# rfid-shield.net
KiCad netlist of a schematic drawn in EAGLE
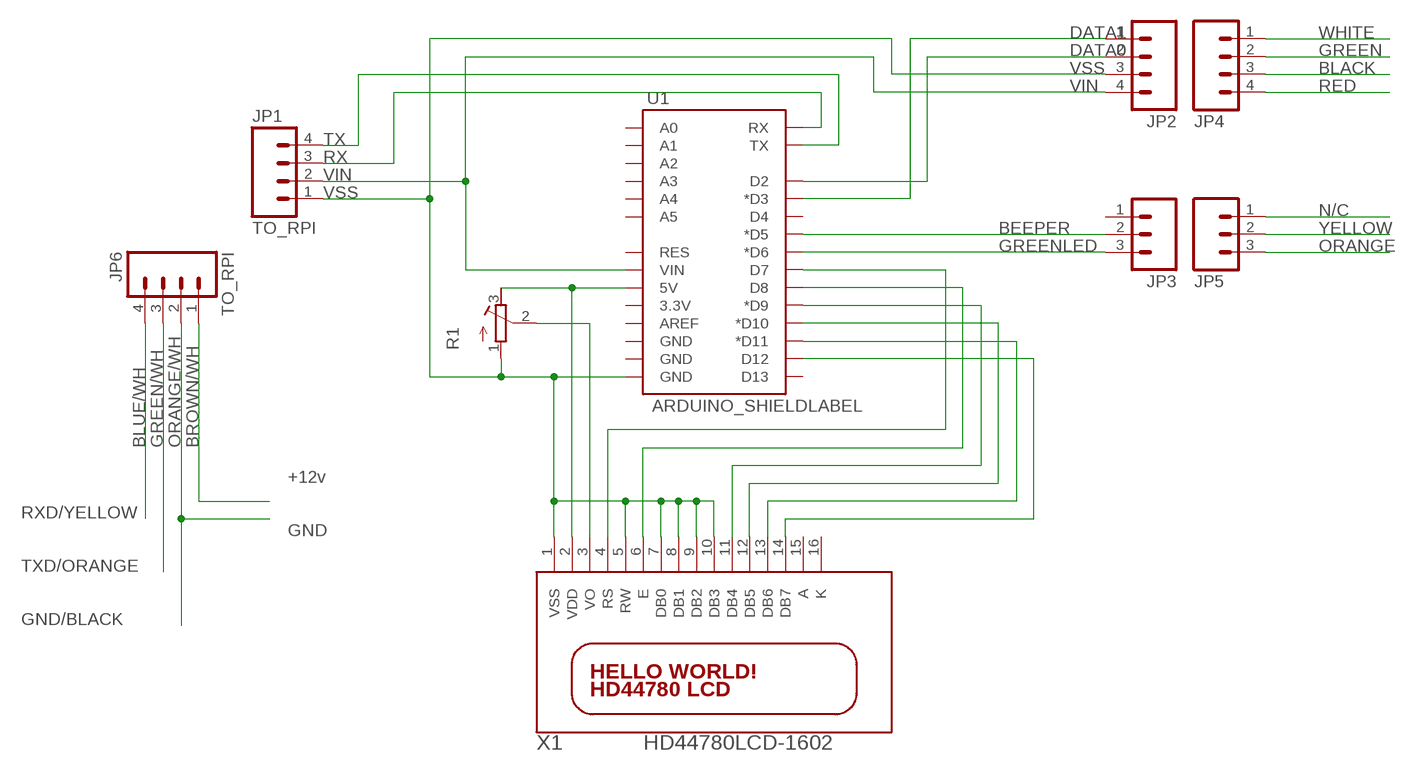
[diagram p0: schematic, sheet 1]

(export (version "E")
  (design (tool "Eeschema 10.0.6"))
  (components
    (comp (ref "JP1")
      (value "TO_RPI")
      (footprint "eagle-import:1X04_NO_SILK")
      (libsource (lib "eagle-import") (part "M041X04_NO_SILK"))
    )
    (comp (ref "JP2")
      (value "M041X04_NO_SILK")
      (footprint "eagle-import:1X04_NO_SILK")
      (libsource (lib "eagle-import") (part "M041X04_NO_SILK"))
    )
    (comp (ref "JP3")
      (value "M031X03_NO_SILK")
      (footprint "eagle-import:1X03_NO_SILK")
      (libsource (lib "eagle-import") (part "M031X03_NO_SILK"))
    )
    (comp (ref "JP4")
      (value "M041X04_NO_SILK")
      (footprint "eagle-import:1X04_NO_SILK")
      (libsource (lib "eagle-import") (part "M041X04_NO_SILK"))
    )
    (comp (ref "JP5")
      (value "M031X03_NO_SILK")
      (footprint "eagle-import:1X03_NO_SILK")
      (libsource (lib "eagle-import") (part "M031X03_NO_SILK"))
    )
    (comp (ref "JP6")
      (value "TO_RPI")
      (footprint "eagle-import:1X04_NO_SILK")
      (libsource (lib "eagle-import") (part "M041X04_NO_SILK"))
    )
    (comp (ref "R1")
      (value "R-TRIMMCVR42A")
      (footprint "eagle-import:RTRIMCVR42A")
      (libsource (lib "eagle-import") (part "R-TRIMMCVR42A"))
    )
    (comp (ref "U1")
      (value "ARDUINO_SHIELDLABEL")
      (footprint "eagle-import:DUEMILANOVE_SHIELD")
      (libsource (lib "eagle-import") (part "ARDUINO_SHIELDLABEL"))
    )
    (comp (ref "X1")
      (value "HD44780LCD-1602")
      (footprint "eagle-import:LCD1602")
      (libsource (lib "eagle-import") (part "HD44780LCD-1602"))
    )
  )
  (nets
    (net (code "1") (name "/BEEPER") (class "Default")
      (node (ref "JP3") (pin "2") (pinfunction "2_2") (pintype "passive"))
      (node (ref "U1") (pin "D5") (pinfunction "*D5_D5") (pintype "bidirectional"))
    )
    (net (code "2") (name "/BLACK") (class "Default")
      (node (ref "JP4") (pin "3") (pinfunction "3_3") (pintype "passive"))
    )
    (net (code "3") (name "/BLUE{slash}WH") (class "Default")
      (node (ref "JP6") (pin "4") (pinfunction "4_4") (pintype "passive"))
    )
    (net (code "4") (name "/BROWN{slash}WH") (class "Default")
      (node (ref "JP6") (pin "1") (pinfunction "1_1") (pintype "passive"))
    )
    (net (code "5") (name "/DATA0") (class "Default")
      (node (ref "JP2") (pin "2") (pinfunction "2_2") (pintype "passive"))
      (node (ref "U1") (pin "D2") (pinfunction "D2_D2") (pintype "bidirectional"))
    )
    (net (code "6") (name "/DATA1") (class "Default")
      (node (ref "JP2") (pin "1") (pinfunction "1_1") (pintype "passive"))
      (node (ref "U1") (pin "D3") (pinfunction "*D3_D3") (pintype "bidirectional"))
    )
    (net (code "7") (name "/GREEN") (class "Default")
      (node (ref "JP4") (pin "2") (pinfunction "2_2") (pintype "passive"))
    )
    (net (code "8") (name "/GREENLED") (class "Default")
      (node (ref "JP3") (pin "3") (pinfunction "3_3") (pintype "passive"))
      (node (ref "U1") (pin "D6") (pinfunction "*D6_D6") (pintype "bidirectional"))
    )
    (net (code "9") (name "/GREEN{slash}WH") (class "Default")
      (node (ref "JP6") (pin "3") (pinfunction "3_3") (pintype "passive"))
    )
    (net (code "10") (name "/N{slash}C") (class "Default")
      (node (ref "JP5") (pin "1") (pinfunction "1_1") (pintype "passive"))
    )
    (net (code "11") (name "/ORANGE") (class "Default")
      (node (ref "JP5") (pin "3") (pinfunction "3_3") (pintype "passive"))
    )
    (net (code "12") (name "/ORANGE{slash}WH") (class "Default")
      (node (ref "JP6") (pin "2") (pinfunction "2_2") (pintype "passive"))
    )
    (net (code "13") (name "/RED") (class "Default")
      (node (ref "JP4") (pin "4") (pinfunction "4_4") (pintype "passive"))
    )
    (net (code "14") (name "/RX") (class "Default")
      (node (ref "JP1") (pin "3") (pinfunction "3_3") (pintype "passive"))
      (node (ref "U1") (pin "RX") (pinfunction "RX_RX") (pintype "bidirectional"))
    )
    (net (code "15") (name "/TX") (class "Default")
      (node (ref "JP1") (pin "4") (pinfunction "4_4") (pintype "passive"))
      (node (ref "U1") (pin "TX") (pinfunction "TX_TX") (pintype "bidirectional"))
    )
    (net (code "16") (name "/VIN") (class "Default")
      (node (ref "JP1") (pin "2") (pinfunction "2_2") (pintype "passive"))
      (node (ref "JP2") (pin "4") (pinfunction "4_4") (pintype "passive"))
      (node (ref "U1") (pin "VIN") (pinfunction "VIN_VIN") (pintype "bidirectional"))
    )
    (net (code "17") (name "/VSS") (class "Default")
      (node (ref "JP1") (pin "1") (pinfunction "1_1") (pintype "passive"))
      (node (ref "JP2") (pin "3") (pinfunction "3_3") (pintype "passive"))
      (node (ref "R1") (pin "1") (pinfunction "A_1") (pintype "passive"))
      (node (ref "U1") (pin "GND@0") (pinfunction "GND_GND@0") (pintype "bidirectional"))
      (node (ref "X1") (pin "1") (pinfunction "VSS_1") (pintype "power_in"))
      (node (ref "X1") (pin "10") (pinfunction "DB3_10") (pintype "bidirectional"))
      (node (ref "X1") (pin "5") (pinfunction "RW_5") (pintype "input"))
      (node (ref "X1") (pin "7") (pinfunction "DB0_7") (pintype "bidirectional"))
      (node (ref "X1") (pin "8") (pinfunction "DB1_8") (pintype "bidirectional"))
      (node (ref "X1") (pin "9") (pinfunction "DB2_9") (pintype "bidirectional"))
    )
    (net (code "18") (name "/WHITE") (class "Default")
      (node (ref "JP4") (pin "1") (pinfunction "1_1") (pintype "passive"))
    )
    (net (code "19") (name "/YELLOW") (class "Default")
      (node (ref "JP5") (pin "2") (pinfunction "2_2") (pintype "passive"))
    )
    (net (code "20") (name "Net-(R1-E)") (class "Default")
      (node (ref "R1") (pin "3") (pinfunction "E_3") (pintype "passive"))
      (node (ref "U1") (pin "5V") (pinfunction "5V_5V") (pintype "bidirectional"))
      (node (ref "X1") (pin "2") (pinfunction "VDD_2") (pintype "power_in"))
    )
    (net (code "21") (name "Net-(R1-S)") (class "Default")
      (node (ref "R1") (pin "2") (pinfunction "S_2") (pintype "passive"))
      (node (ref "X1") (pin "3") (pinfunction "VO_3") (pintype "input"))
    )
    (net (code "22") (name "Net-(U1-*D9)") (class "Default")
      (node (ref "U1") (pin "D9") (pinfunction "*D9_D9") (pintype "bidirectional"))
      (node (ref "X1") (pin "11") (pinfunction "DB4_11") (pintype "bidirectional"))
    )
    (net (code "23") (name "Net-(U1-*D10)") (class "Default")
      (node (ref "U1") (pin "D10") (pinfunction "*D10_D10") (pintype "bidirectional"))
      (node (ref "X1") (pin "12") (pinfunction "DB5_12") (pintype "bidirectional"))
    )
    (net (code "24") (name "Net-(U1-*D11)") (class "Default")
      (node (ref "U1") (pin "D11") (pinfunction "*D11_D11") (pintype "bidirectional"))
      (node (ref "X1") (pin "13") (pinfunction "DB6_13") (pintype "bidirectional"))
    )
    (net (code "25") (name "Net-(X1-DB7)") (class "Default")
      (node (ref "U1") (pin "D12") (pinfunction "D12_D12") (pintype "bidirectional"))
      (node (ref "X1") (pin "14") (pinfunction "DB7_14") (pintype "bidirectional"))
    )
    (net (code "26") (name "Net-(X1-E)") (class "Default")
      (node (ref "U1") (pin "D8") (pinfunction "D8_D8") (pintype "bidirectional"))
      (node (ref "X1") (pin "6") (pinfunction "E_6") (pintype "input"))
    )
    (net (code "27") (name "Net-(X1-RS)") (class "Default")
      (node (ref "U1") (pin "D7") (pinfunction "D7_D7") (pintype "bidirectional"))
      (node (ref "X1") (pin "4") (pinfunction "RS_4") (pintype "input"))
    )
    (net (code "28") (name "unconnected-(JP3-Pad1)") (class "Default")
      (node (ref "JP3") (pin "1") (pinfunction "1_1") (pintype "passive"))
    )
    (net (code "29") (name "unconnected-(U1-GND-PadGND@1)") (class "Default")
      (node (ref "U1") (pin "GND@1") (pinfunction "GND_GND@1") (pintype "bidirectional"))
    )
    (net (code "30") (name "unconnected-(U1-GND-PadGND@2)") (class "Default")
      (node (ref "U1") (pin "GND@2") (pinfunction "GND_GND@2") (pintype "bidirectional"))
    )
    (net (code "31") (name "unconnected-(U1-Pad3.3V)") (class "Default")
      (node (ref "U1") (pin "3.3V") (pinfunction "3.3V_3.3V") (pintype "bidirectional"))
    )
    (net (code "32") (name "unconnected-(U1-PadA0)") (class "Default")
      (node (ref "U1") (pin "A0") (pinfunction "A0_A0") (pintype "bidirectional"))
    )
    (net (code "33") (name "unconnected-(U1-PadA1)") (class "Default")
      (node (ref "U1") (pin "A1") (pinfunction "A1_A1") (pintype "bidirectional"))
    )
    (net (code "34") (name "unconnected-(U1-PadA2)") (class "Default")
      (node (ref "U1") (pin "A2") (pinfunction "A2_A2") (pintype "bidirectional"))
    )
    (net (code "35") (name "unconnected-(U1-PadA3)") (class "Default")
      (node (ref "U1") (pin "A3") (pinfunction "A3_A3") (pintype "bidirectional"))
    )
    (net (code "36") (name "unconnected-(U1-PadA4)") (class "Default")
      (node (ref "U1") (pin "A4") (pinfunction "A4_A4") (pintype "bidirectional"))
    )
    (net (code "37") (name "unconnected-(U1-PadA5)") (class "Default")
      (node (ref "U1") (pin "A5") (pinfunction "A5_A5") (pintype "bidirectional"))
    )
    (net (code "38") (name "unconnected-(U1-PadAREF)") (class "Default")
      (node (ref "U1") (pin "AREF") (pinfunction "AREF_AREF") (pintype "bidirectional"))
    )
    (net (code "39") (name "unconnected-(U1-PadD4)") (class "Default")
      (node (ref "U1") (pin "D4") (pinfunction "D4_D4") (pintype "bidirectional"))
    )
    (net (code "40") (name "unconnected-(U1-PadD13)") (class "Default")
      (node (ref "U1") (pin "D13") (pinfunction "D13_D13") (pintype "bidirectional"))
    )
    (net (code "41") (name "unconnected-(U1-PadRES)") (class "Default")
      (node (ref "U1") (pin "RES") (pinfunction "RES_RES") (pintype "bidirectional"))
    )
    (net (code "42") (name "unconnected-(X1-A-Pad15)") (class "Default")
      (node (ref "X1") (pin "15") (pinfunction "A_15") (pintype "input"))
    )
    (net (code "43") (name "unconnected-(X1-K-Pad16)") (class "Default")
      (node (ref "X1") (pin "16") (pinfunction "K_16") (pintype "input"))
    )
  )
)
